# SCH_tic-toc_2024-06-27.net
KiCad netlist of a schematic drawn in EasyEDA
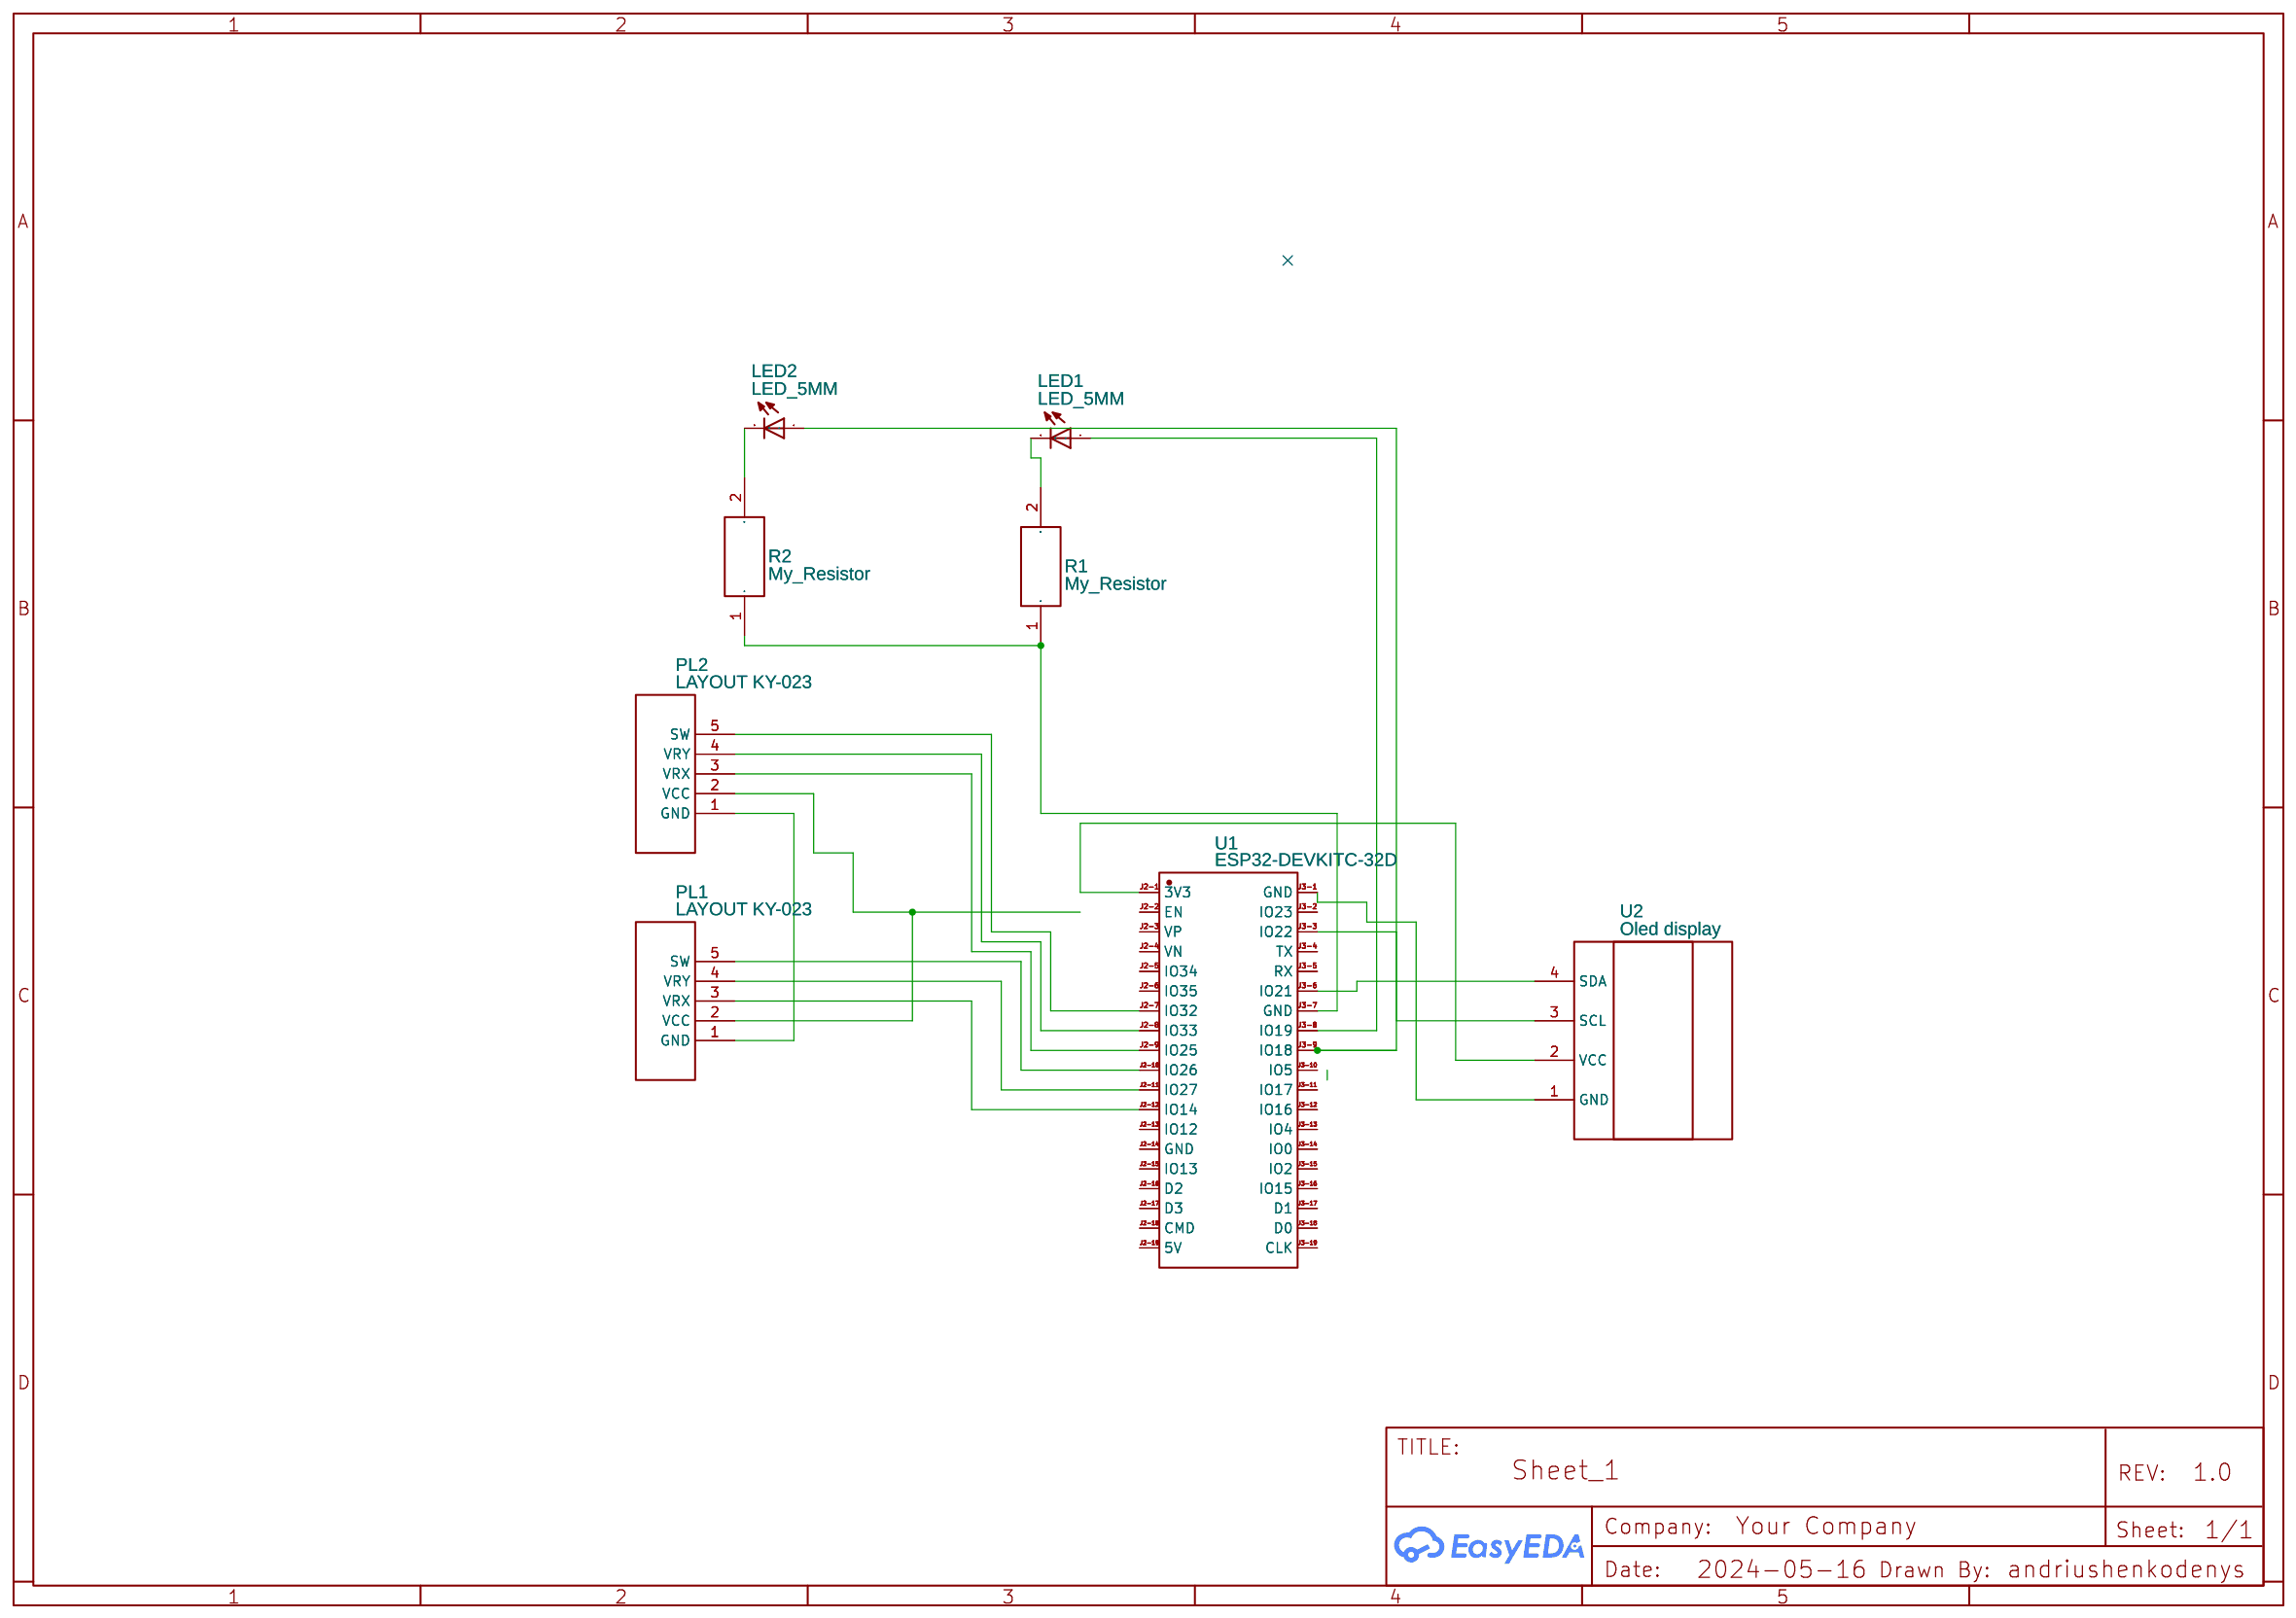
[diagram p0: schematic sheet]

(export (version "E")
  (design (tool "Eeschema 10.0.6"))
  (components
    (comp (ref "LED1") (value "LED_5MM") (libsource (lib "") (part "LED_5MM")))
    (comp (ref "LED2") (value "LED_5MM") (libsource (lib "") (part "LED_5MM")))
    (comp (ref "PL1") (value "LAYOUT KY-023") (libsource (lib "") (part "LAYOUT KY-023")))
    (comp (ref "PL2") (value "LAYOUT KY-023") (libsource (lib "") (part "LAYOUT KY-023")))
    (comp (ref "R1") (value "My_Resistor") (libsource (lib "") (part "My_Resistor")))
    (comp (ref "R2") (value "My_Resistor") (libsource (lib "") (part "My_Resistor")))
    (comp (ref "U1")
      (value "ESP32-DEVKITC-32D")
      (fields
        (field (name "Manufacturer Part") "ESP32-DevKitC-32D")
        (field (name "Manufacturer") "ESPRESSIF(乐鑫)")
      )
      (libsource (lib "") (part "ESP32-DEVKITC-32D"))
    )
    (comp (ref "U2") (value "Oled display") (libsource (lib "") (part "Oled display")))
  )
  (nets
    (net (code "1") (name "Net-(LED1-A)") (class "Default")
      (node (ref "LED1") (pin "1") (pinfunction "A_1") (pintype "unspecified"))
      (node (ref "U1") (pin "J3-8") (pinfunction "IO19_J3-8") (pintype "unspecified"))
    )
    (net (code "2") (name "Net-(LED1-C)") (class "Default")
      (node (ref "LED1") (pin "2") (pinfunction "C_2") (pintype "unspecified"))
      (node (ref "R1") (pin "2") (pinfunction "2_2") (pintype "unspecified"))
    )
    (net (code "3") (name "Net-(LED2-A)") (class "Default")
      (node (ref "LED2") (pin "1") (pinfunction "A_1") (pintype "unspecified"))
      (node (ref "U1") (pin "J3-9") (pinfunction "IO18_J3-9") (pintype "unspecified"))
    )
    (net (code "4") (name "Net-(LED2-C)") (class "Default")
      (node (ref "LED2") (pin "2") (pinfunction "C_2") (pintype "unspecified"))
      (node (ref "R2") (pin "2") (pinfunction "2_2") (pintype "unspecified"))
    )
    (net (code "5") (name "Net-(PL1-GND)") (class "Default")
      (node (ref "PL1") (pin "1") (pinfunction "GND_1") (pintype "unspecified"))
      (node (ref "PL2") (pin "1") (pinfunction "GND_1") (pintype "unspecified"))
    )
    (net (code "6") (name "Net-(PL1-SW)") (class "Default")
      (node (ref "PL1") (pin "5") (pinfunction "SW_5") (pintype "unspecified"))
      (node (ref "U1") (pin "J2-10") (pinfunction "IO26_J2-10") (pintype "unspecified"))
    )
    (net (code "7") (name "Net-(PL1-VCC)") (class "Default")
      (node (ref "PL1") (pin "2") (pinfunction "VCC_2") (pintype "unspecified"))
      (node (ref "PL2") (pin "2") (pinfunction "VCC_2") (pintype "unspecified"))
    )
    (net (code "8") (name "Net-(PL1-VRX)") (class "Default")
      (node (ref "PL1") (pin "3") (pinfunction "VRX_3") (pintype "unspecified"))
      (node (ref "U1") (pin "J2-12") (pinfunction "IO14_J2-12") (pintype "unspecified"))
    )
    (net (code "9") (name "Net-(PL1-VRY)") (class "Default")
      (node (ref "PL1") (pin "4") (pinfunction "VRY_4") (pintype "unspecified"))
      (node (ref "U1") (pin "J2-11") (pinfunction "IO27_J2-11") (pintype "unspecified"))
    )
    (net (code "10") (name "Net-(PL2-SW)") (class "Default")
      (node (ref "PL2") (pin "5") (pinfunction "SW_5") (pintype "unspecified"))
      (node (ref "U1") (pin "J2-7") (pinfunction "IO32_J2-7") (pintype "unspecified"))
    )
    (net (code "11") (name "Net-(PL2-VRX)") (class "Default")
      (node (ref "PL2") (pin "3") (pinfunction "VRX_3") (pintype "unspecified"))
      (node (ref "U1") (pin "J2-9") (pinfunction "IO25_J2-9") (pintype "unspecified"))
    )
    (net (code "12") (name "Net-(PL2-VRY)") (class "Default")
      (node (ref "PL2") (pin "4") (pinfunction "VRY_4") (pintype "unspecified"))
      (node (ref "U1") (pin "J2-8") (pinfunction "IO33_J2-8") (pintype "unspecified"))
    )
    (net (code "13") (name "Net-(R1-Pad1)") (class "Default")
      (node (ref "R1") (pin "1") (pinfunction "1_1") (pintype "unspecified"))
      (node (ref "R2") (pin "1") (pinfunction "1_1") (pintype "unspecified"))
      (node (ref "U1") (pin "J3-7") (pinfunction "GND_J3-7") (pintype "unspecified"))
    )
    (net (code "14") (name "Net-(U1-3V3)") (class "Default")
      (node (ref "U1") (pin "J2-1") (pinfunction "3V3_J2-1") (pintype "unspecified"))
      (node (ref "U2") (pin "2") (pinfunction "VCC_2") (pintype "unspecified"))
    )
    (net (code "15") (name "Net-(U1-IO21)") (class "Default")
      (node (ref "U1") (pin "J3-6") (pinfunction "IO21_J3-6") (pintype "unspecified"))
      (node (ref "U2") (pin "4") (pinfunction "SDA_4") (pintype "unspecified"))
    )
    (net (code "16") (name "Net-(U1-IO22)") (class "Default")
      (node (ref "U1") (pin "J3-3") (pinfunction "IO22_J3-3") (pintype "unspecified"))
      (node (ref "U2") (pin "3") (pinfunction "SCL_3") (pintype "unspecified"))
    )
    (net (code "17") (name "Net-(U2-GND)") (class "Default")
      (node (ref "U1") (pin "J3-1") (pinfunction "GND_J3-1") (pintype "unspecified"))
      (node (ref "U2") (pin "1") (pinfunction "GND_1") (pintype "unspecified"))
    )
    (net (code "18") (name "unconnected-(U1-5V-PadJ2-19)") (class "Default")
      (node (ref "U1") (pin "J2-19") (pinfunction "5V_J2-19") (pintype "unspecified"))
    )
    (net (code "19") (name "unconnected-(U1-CLK-PadJ3-19)") (class "Default")
      (node (ref "U1") (pin "J3-19") (pinfunction "CLK_J3-19") (pintype "unspecified"))
    )
    (net (code "20") (name "unconnected-(U1-CMD-PadJ2-18)") (class "Default")
      (node (ref "U1") (pin "J2-18") (pinfunction "CMD_J2-18") (pintype "unspecified"))
    )
    (net (code "21") (name "unconnected-(U1-D0-PadJ3-18)") (class "Default")
      (node (ref "U1") (pin "J3-18") (pinfunction "D0_J3-18") (pintype "unspecified"))
    )
    (net (code "22") (name "unconnected-(U1-D1-PadJ3-17)") (class "Default")
      (node (ref "U1") (pin "J3-17") (pinfunction "D1_J3-17") (pintype "unspecified"))
    )
    (net (code "23") (name "unconnected-(U1-D2-PadJ2-16)") (class "Default")
      (node (ref "U1") (pin "J2-16") (pinfunction "D2_J2-16") (pintype "unspecified"))
    )
    (net (code "24") (name "unconnected-(U1-D3-PadJ2-17)") (class "Default")
      (node (ref "U1") (pin "J2-17") (pinfunction "D3_J2-17") (pintype "unspecified"))
    )
    (net (code "25") (name "unconnected-(U1-EN-PadJ2-2)") (class "Default")
      (node (ref "U1") (pin "J2-2") (pinfunction "EN_J2-2") (pintype "unspecified"))
    )
    (net (code "26") (name "unconnected-(U1-GND-PadJ2-14)") (class "Default")
      (node (ref "U1") (pin "J2-14") (pinfunction "GND_J2-14") (pintype "unspecified"))
    )
    (net (code "27") (name "unconnected-(U1-IO0-PadJ3-14)") (class "Default")
      (node (ref "U1") (pin "J3-14") (pinfunction "IO0_J3-14") (pintype "unspecified"))
    )
    (net (code "28") (name "unconnected-(U1-IO2-PadJ3-15)") (class "Default")
      (node (ref "U1") (pin "J3-15") (pinfunction "IO2_J3-15") (pintype "unspecified"))
    )
    (net (code "29") (name "unconnected-(U1-IO4-PadJ3-13)") (class "Default")
      (node (ref "U1") (pin "J3-13") (pinfunction "IO4_J3-13") (pintype "unspecified"))
    )
    (net (code "30") (name "unconnected-(U1-IO5-PadJ3-10)") (class "Default")
      (node (ref "U1") (pin "J3-10") (pinfunction "IO5_J3-10") (pintype "unspecified"))
    )
    (net (code "31") (name "unconnected-(U1-IO12-PadJ2-13)") (class "Default")
      (node (ref "U1") (pin "J2-13") (pinfunction "IO12_J2-13") (pintype "unspecified"))
    )
    (net (code "32") (name "unconnected-(U1-IO13-PadJ2-15)") (class "Default")
      (node (ref "U1") (pin "J2-15") (pinfunction "IO13_J2-15") (pintype "unspecified"))
    )
    (net (code "33") (name "unconnected-(U1-IO15-PadJ3-16)") (class "Default")
      (node (ref "U1") (pin "J3-16") (pinfunction "IO15_J3-16") (pintype "unspecified"))
    )
    (net (code "34") (name "unconnected-(U1-IO16-PadJ3-12)") (class "Default")
      (node (ref "U1") (pin "J3-12") (pinfunction "IO16_J3-12") (pintype "unspecified"))
    )
    (net (code "35") (name "unconnected-(U1-IO17-PadJ3-11)") (class "Default")
      (node (ref "U1") (pin "J3-11") (pinfunction "IO17_J3-11") (pintype "unspecified"))
    )
    (net (code "36") (name "unconnected-(U1-IO23-PadJ3-2)") (class "Default")
      (node (ref "U1") (pin "J3-2") (pinfunction "IO23_J3-2") (pintype "unspecified"))
    )
    (net (code "37") (name "unconnected-(U1-IO34-PadJ2-5)") (class "Default")
      (node (ref "U1") (pin "J2-5") (pinfunction "IO34_J2-5") (pintype "unspecified"))
    )
    (net (code "38") (name "unconnected-(U1-IO35-PadJ2-6)") (class "Default")
      (node (ref "U1") (pin "J2-6") (pinfunction "IO35_J2-6") (pintype "unspecified"))
    )
    (net (code "39") (name "unconnected-(U1-RX-PadJ3-5)") (class "Default")
      (node (ref "U1") (pin "J3-5") (pinfunction "RX_J3-5") (pintype "unspecified"))
    )
    (net (code "40") (name "unconnected-(U1-TX-PadJ3-4)") (class "Default")
      (node (ref "U1") (pin "J3-4") (pinfunction "TX_J3-4") (pintype "unspecified"))
    )
    (net (code "41") (name "unconnected-(U1-VN-PadJ2-4)") (class "Default")
      (node (ref "U1") (pin "J2-4") (pinfunction "VN_J2-4") (pintype "unspecified"))
    )
    (net (code "42") (name "unconnected-(U1-VP-PadJ2-3)") (class "Default")
      (node (ref "U1") (pin "J2-3") (pinfunction "VP_J2-3") (pintype "unspecified"))
    )
  )
)
